# unipolar_stepp_connect.net
KiCad netlist of a schematic drawn in EAGLE
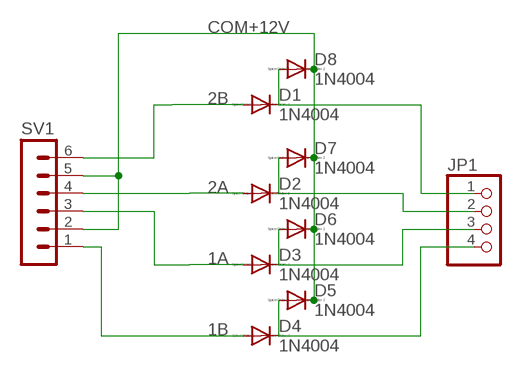
[diagram p0: schematic, sheet 1]

(export (version "E")
  (design (tool "Eeschema 10.0.6"))
  (components
    (comp (ref "D1")
      (value "1N4004")
      (footprint "eagle-import:DO41-10")
      (libsource (lib "eagle-import") (part "1N4004"))
    )
    (comp (ref "D2")
      (value "1N4004")
      (footprint "eagle-import:DO41-10")
      (libsource (lib "eagle-import") (part "1N4004"))
    )
    (comp (ref "D3")
      (value "1N4004")
      (footprint "eagle-import:DO41-10")
      (libsource (lib "eagle-import") (part "1N4004"))
    )
    (comp (ref "D4")
      (value "1N4004")
      (footprint "eagle-import:DO41-10")
      (libsource (lib "eagle-import") (part "1N4004"))
    )
    (comp (ref "D5")
      (value "1N4004")
      (footprint "eagle-import:DO41-10")
      (libsource (lib "eagle-import") (part "1N4004"))
    )
    (comp (ref "D6")
      (value "1N4004")
      (footprint "eagle-import:DO41-10")
      (libsource (lib "eagle-import") (part "1N4004"))
    )
    (comp (ref "D7")
      (value "1N4004")
      (footprint "eagle-import:DO41-10")
      (libsource (lib "eagle-import") (part "1N4004"))
    )
    (comp (ref "D8")
      (value "1N4004")
      (footprint "eagle-import:DO41-10")
      (libsource (lib "eagle-import") (part "1N4004"))
    )
    (comp (ref "JP1")
      (value "PINHD-1X4/90")
      (footprint "eagle-import:1X04_90")
      (libsource (lib "eagle-import") (part "PINHD-1X4/90"))
    )
    (comp (ref "SV1")
      (value "MA06-1")
      (footprint "eagle-import:MA06-1")
      (libsource (lib "eagle-import") (part "MA06-1"))
    )
  )
  (nets
    (net (code "1") (name "/1A") (class "Default")
      (node (ref "D3") (pin "A") (pinfunction "A_A") (pintype "passive"))
      (node (ref "SV1") (pin "3") (pinfunction "3_3") (pintype "passive"))
    )
    (net (code "2") (name "/1B") (class "Default")
      (node (ref "D4") (pin "A") (pinfunction "A_A") (pintype "passive"))
      (node (ref "SV1") (pin "1") (pinfunction "1_1") (pintype "passive"))
    )
    (net (code "3") (name "/2A") (class "Default")
      (node (ref "D2") (pin "A") (pinfunction "A_A") (pintype "passive"))
      (node (ref "SV1") (pin "4") (pinfunction "4_4") (pintype "passive"))
    )
    (net (code "4") (name "/2B") (class "Default")
      (node (ref "D1") (pin "A") (pinfunction "A_A") (pintype "passive"))
      (node (ref "SV1") (pin "6") (pinfunction "6_6") (pintype "passive"))
    )
    (net (code "5") (name "/COM+12V") (class "Default")
      (node (ref "D5") (pin "C") (pinfunction "C_C") (pintype "passive"))
      (node (ref "D6") (pin "C") (pinfunction "C_C") (pintype "passive"))
      (node (ref "D7") (pin "C") (pinfunction "C_C") (pintype "passive"))
      (node (ref "D8") (pin "C") (pinfunction "C_C") (pintype "passive"))
      (node (ref "SV1") (pin "2") (pinfunction "2_2") (pintype "passive"))
      (node (ref "SV1") (pin "5") (pinfunction "5_5") (pintype "passive"))
    )
    (net (code "6") (name "Net-(D1-PadC)") (class "Default")
      (node (ref "D1") (pin "C") (pinfunction "C_C") (pintype "passive"))
      (node (ref "D8") (pin "A") (pinfunction "A_A") (pintype "passive"))
      (node (ref "JP1") (pin "1") (pinfunction "1_1") (pintype "passive"))
    )
    (net (code "7") (name "Net-(D2-PadC)") (class "Default")
      (node (ref "D2") (pin "C") (pinfunction "C_C") (pintype "passive"))
      (node (ref "D7") (pin "A") (pinfunction "A_A") (pintype "passive"))
      (node (ref "JP1") (pin "2") (pinfunction "2_2") (pintype "passive"))
    )
    (net (code "8") (name "Net-(D3-PadC)") (class "Default")
      (node (ref "D3") (pin "C") (pinfunction "C_C") (pintype "passive"))
      (node (ref "D6") (pin "A") (pinfunction "A_A") (pintype "passive"))
      (node (ref "JP1") (pin "3") (pinfunction "3_3") (pintype "passive"))
    )
    (net (code "9") (name "Net-(D4-PadC)") (class "Default")
      (node (ref "D4") (pin "C") (pinfunction "C_C") (pintype "passive"))
      (node (ref "D5") (pin "A") (pinfunction "A_A") (pintype "passive"))
      (node (ref "JP1") (pin "4") (pinfunction "4_4") (pintype "passive"))
    )
  )
)
